# RejsaCAN_v2_5_-_Schematic.net
KiCad netlist of a schematic drawn in EasyEDA
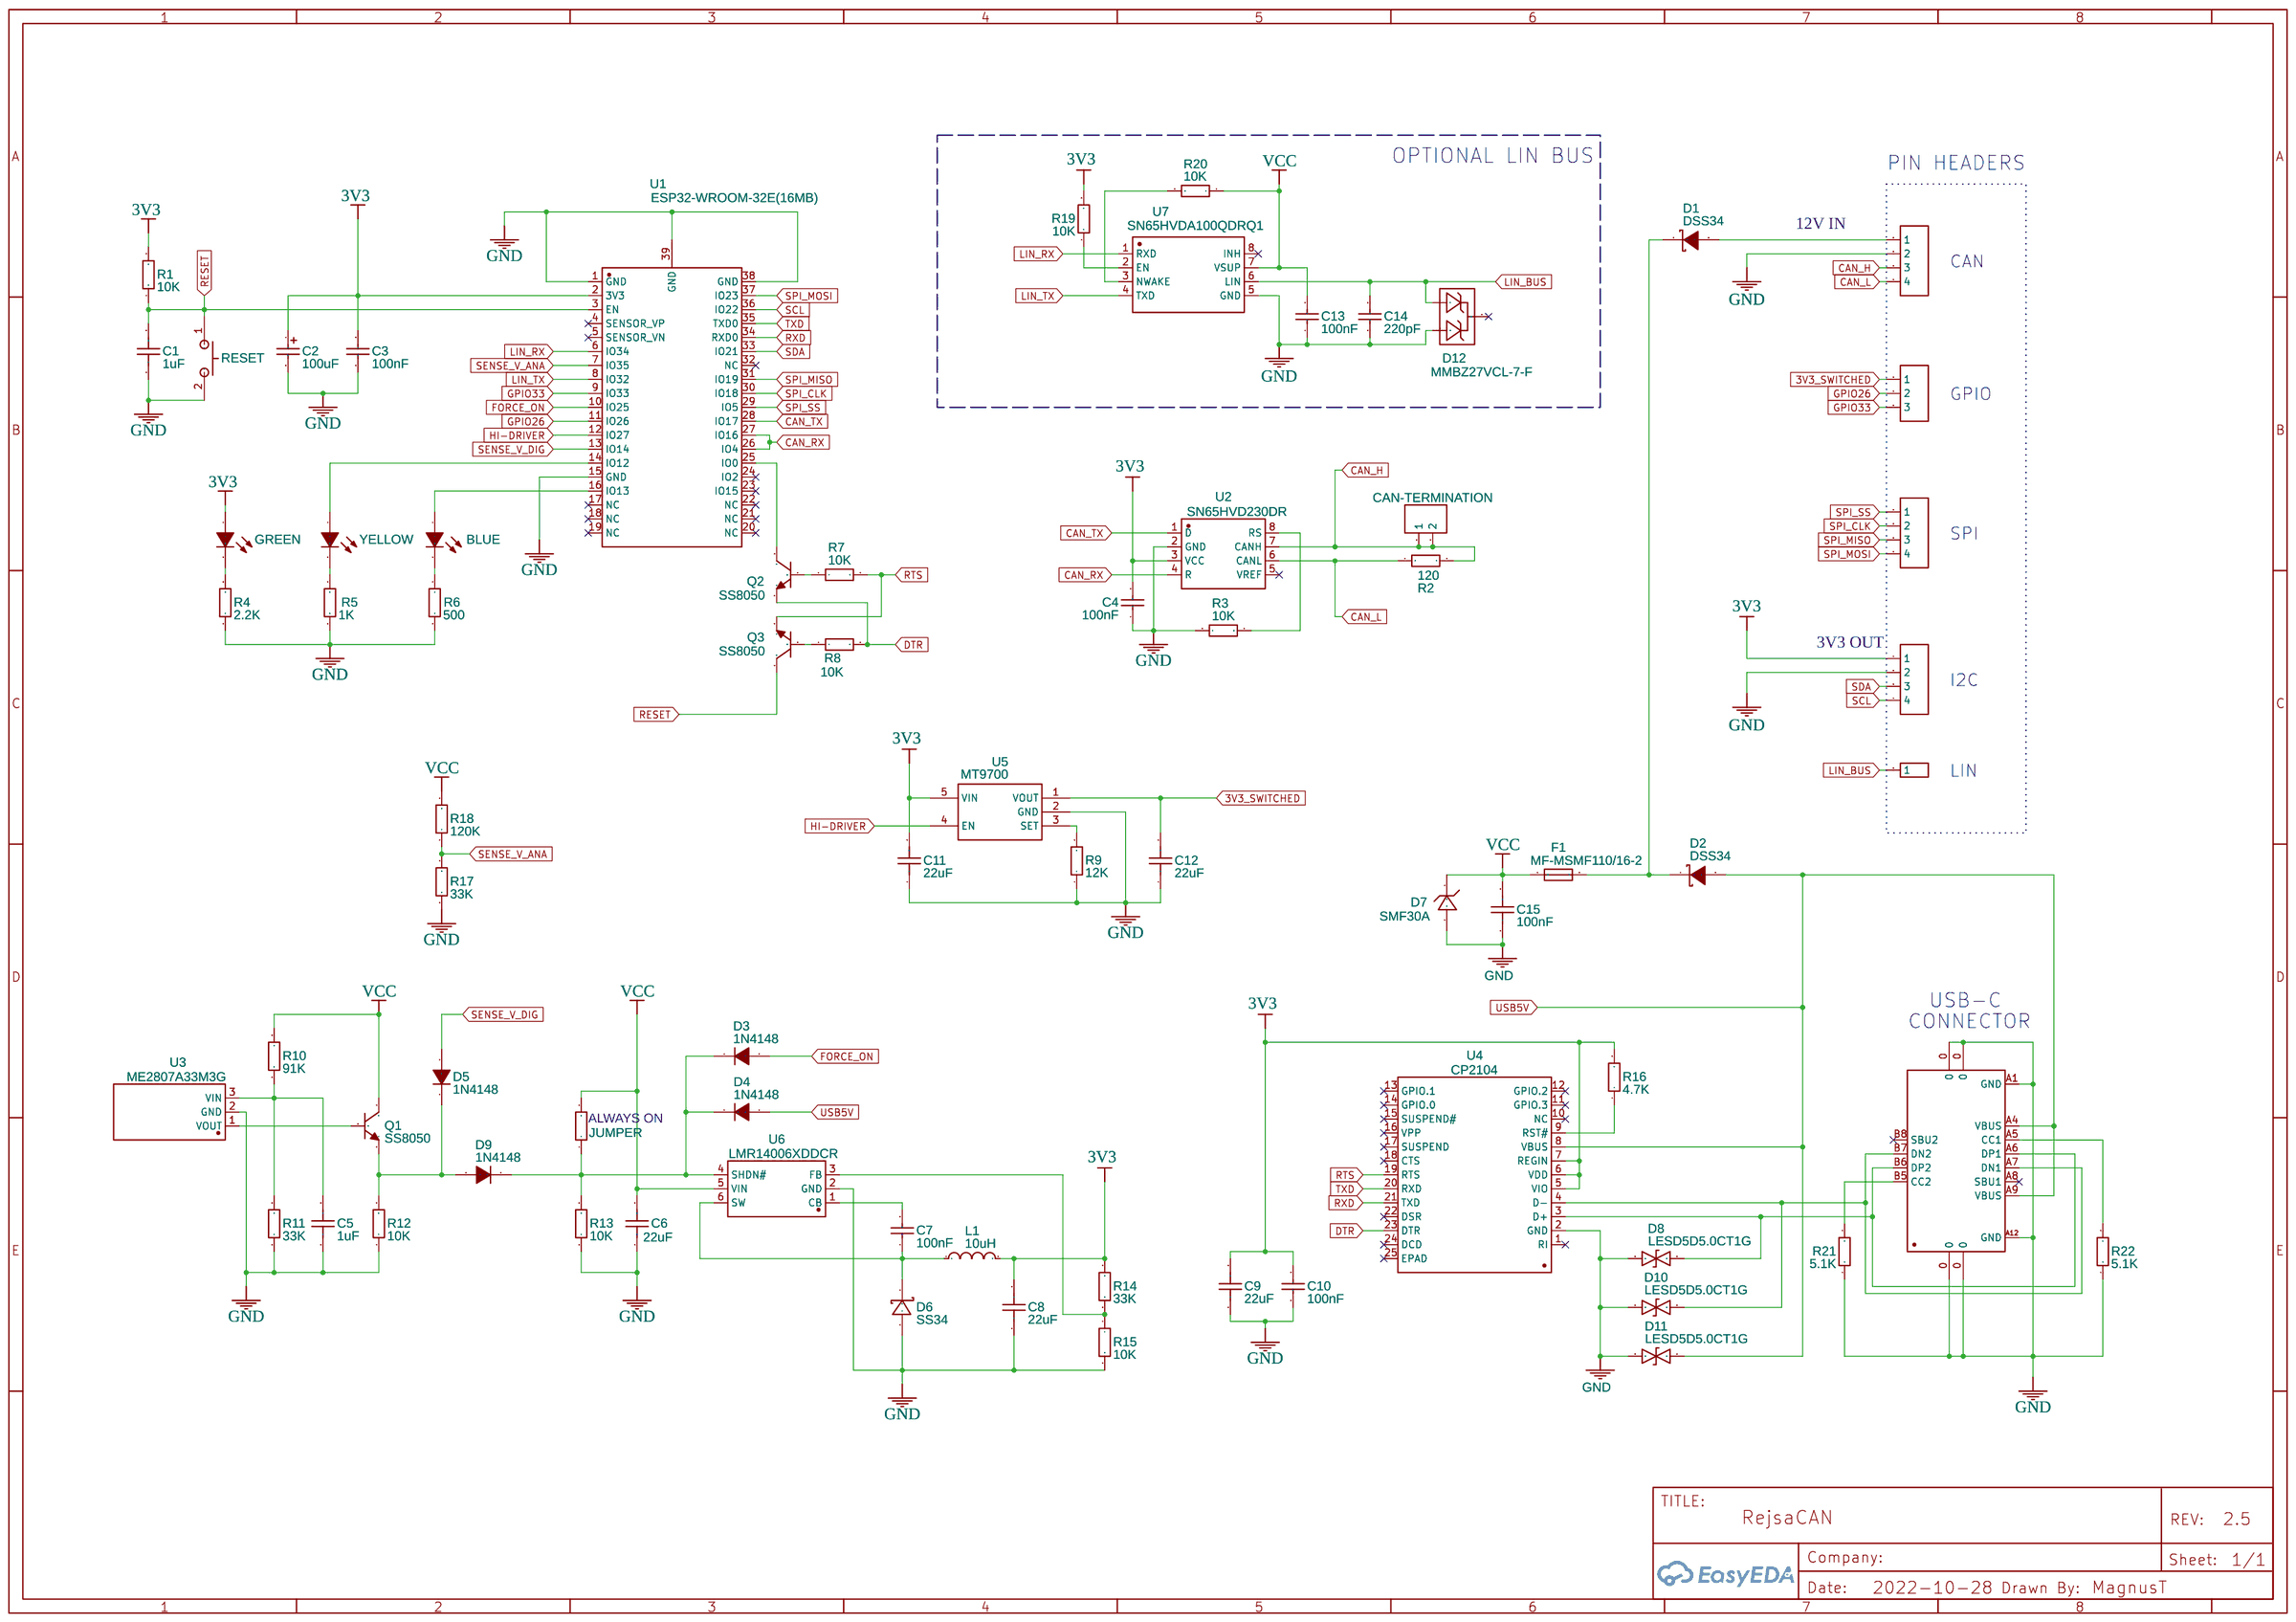
[diagram p0: schematic sheet]

(export (version "E")
  (design (tool "Eeschema 10.0.6"))
  (components
    (comp (ref "BLUE")
      (value "19-217/BHC-ZL1M2RY/3T")
      (fields (field (name "Manufacturer") "EVERLIGHT"))
      (libsource (lib "") (part "19-217/BHC-ZL1M2RY/3T"))
    )
    (comp (ref "C1")
      (value "1uF")
      (fields (field (name "Manufacturer Part") "CL05A105KA5NQNC") (field (name "Manufacturer") "SAMSUNG"))
      (libsource (lib "") (part "CL05A105KA5NQNC"))
    )
    (comp (ref "C2")
      (value "100uF")
      (fields (field (name "Manufacturer Part") "TAJB107K006RNJ") (field (name "Manufacturer") "AVX"))
      (libsource (lib "") (part "TAJB107K006RNJ"))
    )
    (comp (ref "C3")
      (value "100nF")
      (fields (field (name "Manufacturer Part") "CL05B104KO5NNNC") (field (name "Manufacturer") "SAMSUNG"))
      (libsource (lib "") (part "CL05B104KO5NNNC_1"))
    )
    (comp (ref "C4")
      (value "100nF")
      (fields (field (name "Manufacturer Part") "CL05B104KO5NNNC") (field (name "Manufacturer") "SAMSUNG"))
      (libsource (lib "") (part "CL05B104KO5NNNC"))
    )
    (comp (ref "C5")
      (value "1uF")
      (fields (field (name "Manufacturer Part") "CL05A105KA5NQNC") (field (name "Manufacturer") "SAMSUNG"))
      (libsource (lib "") (part "CL05A105KA5NQNC"))
    )
    (comp (ref "C6")
      (value "22uF")
      (fields
        (field (name "Manufacturer Part") "CL21A226MAYNNNE")
        (field (name "Manufacturer") "Samsung Electro-Mechanics")
      )
      (libsource (lib "") (part "CL21A226MAYNNNE"))
    )
    (comp (ref "C7")
      (value "100nF")
      (fields (field (name "Manufacturer Part") "CL05B104KO5NNNC") (field (name "Manufacturer") "SAMSUNG"))
      (libsource (lib "") (part "CL05B104KO5NNNC_1"))
    )
    (comp (ref "C8")
      (value "22uF")
      (fields (field (name "Manufacturer Part") "CL10A226MQ8NRNC") (field (name "Manufacturer") "SAMSUNG"))
      (libsource (lib "") (part "CL10A226MQ8NRNC"))
    )
    (comp (ref "C9")
      (value "22uF")
      (fields (field (name "Manufacturer Part") "CL10A226MQ8NRNC") (field (name "Manufacturer") "SAMSUNG"))
      (libsource (lib "") (part "CL10A226MQ8NRNC"))
    )
    (comp (ref "C10")
      (value "100nF")
      (fields (field (name "Manufacturer Part") "CL05B104KO5NNNC") (field (name "Manufacturer") "SAMSUNG"))
      (libsource (lib "") (part "CL05B104KO5NNNC_1"))
    )
    (comp (ref "C11")
      (value "22uF")
      (fields (field (name "Manufacturer Part") "CL10A226MQ8NRNC") (field (name "Manufacturer") "SAMSUNG"))
      (libsource (lib "") (part "CL10A226MQ8NRNC"))
    )
    (comp (ref "C12")
      (value "22uF")
      (fields (field (name "Manufacturer Part") "CL10A226MQ8NRNC") (field (name "Manufacturer") "SAMSUNG"))
      (libsource (lib "") (part "CL10A226MQ8NRNC"))
    )
    (comp (ref "C13")
      (value "100nF")
      (fields (field (name "Manufacturer Part") "CL05B104KO5NNNC") (field (name "Manufacturer") "SAMSUNG"))
      (libsource (lib "") (part "CL05B104KO5NNNC_1"))
    )
    (comp (ref "C14")
      (value "220pF")
      (fields (field (name "Manufacturer Part") "0402B221K500NT") (field (name "Manufacturer") "FH"))
      (libsource (lib "") (part "0402B221K500NT"))
    )
    (comp (ref "C15")
      (value "100nF")
      (fields
        (field (name "Manufacturer Part") "CL05B104KB54PNC")
        (field (name "Manufacturer") "Samsung Electro-Mechanics")
      )
      (libsource (lib "") (part "CL05B104KB54PNC"))
    )
    (comp (ref "CAN-TERMINATION") (value "HDR-M-2.54_1x2") (libsource (lib "") (part "HDR-M-2.54_1x2")))
    (comp (ref "D1")
      (value "DSS34")
      (fields (field (name "Manufacturer") "STARSEA"))
      (libsource (lib "") (part "DSS34"))
    )
    (comp (ref "D2")
      (value "DSS34")
      (fields (field (name "Manufacturer") "STARSEA"))
      (libsource (lib "") (part "DSS34"))
    )
    (comp (ref "D3")
      (value "1N4148")
      (fields (field (name "Manufacturer Part") "1N4148WS T4") (field (name "Manufacturer") "CJ"))
      (libsource (lib "") (part "1N4148WS T4"))
    )
    (comp (ref "D4")
      (value "1N4148")
      (fields (field (name "Manufacturer Part") "1N4148WS T4") (field (name "Manufacturer") "CJ"))
      (libsource (lib "") (part "1N4148WS T4"))
    )
    (comp (ref "D5")
      (value "1N4148")
      (fields (field (name "Manufacturer Part") "1N4148WS T4") (field (name "Manufacturer") "CJ"))
      (libsource (lib "") (part "1N4148WS T4_2"))
    )
    (comp (ref "D6")
      (value "SS34")
      (fields (field (name "Manufacturer") "MDD"))
      (libsource (lib "") (part "SS34_C8678"))
    )
    (comp (ref "D7")
      (value "SMF30A")
      (fields (field (name "Manufacturer") "DOWO"))
      (libsource (lib "") (part "SMF30A_C366558"))
    )
    (comp (ref "D8")
      (value "LESD5D5.0CT1G")
      (fields (field (name "Manufacturer") "Leshan Radio"))
      (libsource (lib "") (part "LESD5D5.0CT1G"))
    )
    (comp (ref "D9")
      (value "1N4148")
      (fields (field (name "Manufacturer Part") "1N4148WS T4") (field (name "Manufacturer") "CJ"))
      (libsource (lib "") (part "1N4148WS T4_1"))
    )
    (comp (ref "D10")
      (value "LESD5D5.0CT1G")
      (fields (field (name "Manufacturer") "Leshan Radio"))
      (libsource (lib "") (part "LESD5D5.0CT1G"))
    )
    (comp (ref "D11")
      (value "LESD5D5.0CT1G")
      (fields (field (name "Manufacturer") "Leshan Radio"))
      (libsource (lib "") (part "LESD5D5.0CT1G"))
    )
    (comp (ref "D12")
      (value "MMBZ27VCL-7-F")
      (fields (field (name "Manufacturer") "Diodes Incorporated"))
      (libsource (lib "") (part "MMBZ27VCL-7-F"))
    )
    (comp (ref "F1")
      (value "MF-MSMF110/16-2")
      (fields (field (name "Manufacturer") "BOURNS"))
      (libsource (lib "") (part "MF-MSMF110/16-2"))
    )
    (comp (ref "GREEN")
      (value "19-217/GHC-YR1S2/3T")
      (fields (field (name "Manufacturer") "EVERLIGHT"))
      (libsource (lib "") (part "19-217/GHC-YR1S2/3T"))
    )
    (comp (ref "J1") (value "HDR-M-2.54_1x4") (libsource (lib "") (part "HDR-M-2.54_1x4")))
    (comp (ref "J2") (value "HDR-M-2.54_1x4") (libsource (lib "") (part "HDR-M-2.54_1x4")))
    (comp (ref "J3") (value "HDR-M-2.54_1x4") (libsource (lib "") (part "HDR-M-2.54_1x4")))
    (comp (ref "J4") (value "HDR-M-2.54_1x3") (libsource (lib "") (part "HDR-M-2.54_1x3")))
    (comp (ref "J5") (value "HDR-M-2.54_1x1") (libsource (lib "") (part "HDR-M-2.54_1x1")))
    (comp (ref "JUMPER") (value "-") (libsource (lib "") (part "0402WGF3092TCE")))
    (comp (ref "L1")
      (value "10uH")
      (fields
        (field (name "Manufacturer Part") "SLP6028S100MTT")
        (field (name "Manufacturer") "Sunltech Tech")
      )
      (libsource (lib "") (part "SLP6028S100MTT"))
    )
    (comp (ref "Q1")
      (value "SS8050")
      (fields (field (name "Manufacturer") "CJ"))
      (libsource (lib "") (part "SS8050_C2150_2"))
    )
    (comp (ref "Q2")
      (value "SS8050")
      (fields (field (name "Manufacturer") "CJ"))
      (libsource (lib "") (part "SS8050_C2150_1"))
    )
    (comp (ref "Q3")
      (value "SS8050")
      (fields (field (name "Manufacturer") "CJ"))
      (libsource (lib "") (part "SS8050_C2150"))
    )
    (comp (ref "R1")
      (value "10K")
      (fields (field (name "Manufacturer Part") "0402WGF1002TCE") (field (name "Manufacturer") "UniOhm"))
      (libsource (lib "") (part "0402WGF1002TCE"))
    )
    (comp (ref "R2")
      (value "120")
      (fields (field (name "Manufacturer Part") "RTT061200FTP") (field (name "Manufacturer") "RALEC"))
      (libsource (lib "") (part "RTT061200FTP"))
    )
    (comp (ref "R3")
      (value "10K")
      (fields (field (name "Manufacturer Part") "0402WGF1002TCE") (field (name "Manufacturer") "UniOhm"))
      (libsource (lib "") (part "0402WGF1002TCE_1"))
    )
    (comp (ref "R4")
      (value "2.2K")
      (fields (field (name "Manufacturer Part") "0402WGF2201TCE") (field (name "Manufacturer") "UniOhm"))
      (libsource (lib "") (part "0402WGF2201TCE"))
    )
    (comp (ref "R5")
      (value "1K")
      (fields (field (name "Manufacturer Part") "0402WGF1001TCE") (field (name "Manufacturer") "UniOhm"))
      (libsource (lib "") (part "0402WGF1001TCE"))
    )
    (comp (ref "R6")
      (value "500")
      (fields (field (name "Manufacturer Part") "0402WGF4700TCE") (field (name "Manufacturer") "UniOhm"))
      (libsource (lib "") (part "0402WGF1001TCE"))
    )
    (comp (ref "R7")
      (value "10K")
      (fields (field (name "Manufacturer Part") "0402WGF1002TCE") (field (name "Manufacturer") "UniOhm"))
      (libsource (lib "") (part "0402WGF1002TCE_1"))
    )
    (comp (ref "R8")
      (value "10K")
      (fields (field (name "Manufacturer Part") "0402WGF1002TCE") (field (name "Manufacturer") "UniOhm"))
      (libsource (lib "") (part "0402WGF1002TCE_1"))
    )
    (comp (ref "R9")
      (value "12K")
      (fields (field (name "Manufacturer Part") "0402WGF1202TCE") (field (name "Manufacturer") "UniOhm"))
      (libsource (lib "") (part "0402WGF1202TCE"))
    )
    (comp (ref "R10")
      (value "91K")
      (fields (field (name "Manufacturer Part") "0402WGF9102TCE") (field (name "Manufacturer") "UniOhm"))
      (libsource (lib "") (part "0402WGF9102TCE"))
    )
    (comp (ref "R11")
      (value "33K")
      (fields (field (name "Manufacturer Part") "0402WGF3302TCE") (field (name "Manufacturer") "UniOhm"))
      (libsource (lib "") (part "0402WGF3302TCE"))
    )
    (comp (ref "R12")
      (value "10K")
      (fields (field (name "Manufacturer Part") "0402WGF1002TCE") (field (name "Manufacturer") "UniOhm"))
      (libsource (lib "") (part "0402WGF1002TCE"))
    )
    (comp (ref "R13")
      (value "10K")
      (fields (field (name "Manufacturer Part") "0402WGF1002TCE") (field (name "Manufacturer") "UniOhm"))
      (libsource (lib "") (part "0402WGF1002TCE"))
    )
    (comp (ref "R14")
      (value "33K")
      (fields (field (name "Manufacturer Part") "0402WGF3302TCE") (field (name "Manufacturer") "UniOhm"))
      (libsource (lib "") (part "0402WGF3302TCE"))
    )
    (comp (ref "R15")
      (value "10K")
      (fields (field (name "Manufacturer Part") "0402WGF1002TCE") (field (name "Manufacturer") "UniOhm"))
      (libsource (lib "") (part "0402WGF1002TCE_2"))
    )
    (comp (ref "R16")
      (value "4.7K")
      (fields (field (name "Manufacturer Part") "0402WGF4701TCE") (field (name "Manufacturer") "UniOhm"))
      (libsource (lib "") (part "0402WGF4701TCE"))
    )
    (comp (ref "R17")
      (value "33K")
      (fields (field (name "Manufacturer Part") "0402WGF3302TCE") (field (name "Manufacturer") "UniOhm"))
      (libsource (lib "") (part "0402WGF3302TCE"))
    )
    (comp (ref "R18")
      (value "120K")
      (fields (field (name "Manufacturer Part") "0402WGF1203TCE") (field (name "Manufacturer") "UniOhm"))
      (libsource (lib "") (part "0402WGF1203TCE"))
    )
    (comp (ref "R19")
      (value "10K")
      (fields (field (name "Manufacturer Part") "0402WGF1002TCE") (field (name "Manufacturer") "UniOhm"))
      (libsource (lib "") (part "0402WGF1002TCE"))
    )
    (comp (ref "R20")
      (value "10K")
      (fields (field (name "Manufacturer Part") "0402WGF1002TCE") (field (name "Manufacturer") "UniOhm"))
      (libsource (lib "") (part "0402WGF1002TCE_3"))
    )
    (comp (ref "R21")
      (value "5.1K")
      (fields (field (name "Manufacturer Part") "0402WGF5101TCE") (field (name "Manufacturer") "UniOhm"))
      (libsource (lib "") (part "0402WGF5101TCE"))
    )
    (comp (ref "R22")
      (value "5.1K")
      (fields (field (name "Manufacturer Part") "0402WGF5101TCE") (field (name "Manufacturer") "UniOhm"))
      (libsource (lib "") (part "0402WGF5101TCE"))
    )
    (comp (ref "RESET")
      (value "GT-TC029B-H025-L1N")
      (fields (field (name "Manufacturer") "G-Switch"))
      (libsource (lib "") (part "GT-TC029B-H025-L1N"))
    )
    (comp (ref "U1")
      (value "ESP32-WROOM-32E(16MB)")
      (fields (field (name "Manufacturer") "Espressif Systems"))
      (libsource (lib "") (part "ESP32-WROOM-32E(16MB)"))
    )
    (comp (ref "U2")
      (value "SN65HVD230DR")
      (fields (field (name "Manufacturer") "TI"))
      (libsource (lib "") (part "SN65HVD230DR"))
    )
    (comp (ref "U3")
      (value "ME2807A33M3G")
      (fields (field (name "Manufacturer") "Nanjing Micro One Elec"))
      (libsource (lib "") (part "ME2807A33M3G"))
    )
    (comp (ref "U4")
      (value "CP2104")
      (fields (field (name "Manufacturer Part") "CP2104-F03-GM") (field (name "Manufacturer") "SILICON LABS"))
      (libsource (lib "") (part "CP2104-F03-GM"))
    )
    (comp (ref "U5")
      (value "MT9700")
      (fields (field (name "Manufacturer") "AEROSEMI"))
      (libsource (lib "") (part "MT9700"))
    )
    (comp (ref "U6")
      (value "LMR14006XDDCR")
      (fields (field (name "Manufacturer") "Texas Instruments"))
      (libsource (lib "") (part "LMR14006XDDCR"))
    )
    (comp (ref "U7")
      (value "SN65HVDA100QDRQ1")
      (fields (field (name "Manufacturer") "TI"))
      (libsource (lib "") (part "SN65HVDA100QDRQ1"))
    )
    (comp (ref "USB-C")
      (value "USB3.1C16PFSMT")
      (fields (field (name "Manufacturer") "LCSC"))
      (libsource (lib "") (part "USB3.1C16PFSMT"))
    )
    (comp (ref "YELLOW")
      (value "19-213/Y2C-CQ2R2L/3T(CY)")
      (fields (field (name "Manufacturer") "EVERLIGHT"))
      (libsource (lib "") (part "19-213/Y2C-CQ2R2L/3T(CY)"))
    )
  )
  (nets
    (net (code "1") (name "3V3") (class "Default")
      (node (ref "C10") (pin "2") (pinfunction "2_2") (pintype "input"))
      (node (ref "C11") (pin "2") (pinfunction "2_2") (pintype "unspecified"))
      (node (ref "C2") (pin "1") (pinfunction "1_1") (pintype "input"))
      (node (ref "C3") (pin "2") (pinfunction "2_2") (pintype "input"))
      (node (ref "C4") (pin "2") (pinfunction "2_2") (pintype "input"))
      (node (ref "C8") (pin "2") (pinfunction "2_2") (pintype "unspecified"))
      (node (ref "C9") (pin "2") (pinfunction "2_2") (pintype "unspecified"))
      (node (ref "GREEN") (pin "1") (pinfunction "A_1") (pintype "input"))
      (node (ref "J2") (pin "1") (pinfunction "1_1") (pintype "unspecified"))
      (node (ref "L1") (pin "2") (pinfunction "2_2") (pintype "unspecified"))
      (node (ref "R1") (pin "2") (pinfunction "2_2") (pintype "input"))
      (node (ref "R14") (pin "2") (pinfunction "2_2") (pintype "input"))
      (node (ref "R16") (pin "2") (pinfunction "2_2") (pintype "input"))
      (node (ref "R19") (pin "2") (pinfunction "2_2") (pintype "input"))
      (node (ref "U1") (pin "2") (pinfunction "3V3_2") (pintype "unspecified"))
      (node (ref "U2") (pin "3") (pinfunction "VCC_3") (pintype "unspecified"))
      (node (ref "U4") (pin "5") (pinfunction "VIO_5") (pintype "unspecified"))
      (node (ref "U4") (pin "6") (pinfunction "VDD_6") (pintype "unspecified"))
      (node (ref "U4") (pin "7") (pinfunction "REGIN_7") (pintype "unspecified"))
      (node (ref "U5") (pin "5") (pinfunction "VIN_5") (pintype "unspecified"))
    )
    (net (code "2") (name "3V3_SWITCHED") (class "Default")
      (node (ref "C12") (pin "2") (pinfunction "2_2") (pintype "unspecified"))
      (node (ref "J4") (pin "1") (pinfunction "1_1") (pintype "input"))
      (node (ref "U5") (pin "1") (pinfunction "VOUT_1") (pintype "unspecified"))
    )
    (net (code "3") (name "CAN_H") (class "Default")
      (node (ref "CAN-TERMINATION") (pin "1") (pinfunction "1_1") (pintype "unspecified"))
      (node (ref "CAN-TERMINATION") (pin "2") (pinfunction "2_2") (pintype "unspecified"))
      (node (ref "J1") (pin "3") (pinfunction "3_3") (pintype "unspecified"))
      (node (ref "R2") (pin "2") (pinfunction "2_2") (pintype "unspecified"))
      (node (ref "U2") (pin "7") (pinfunction "CANH_7") (pintype "unspecified"))
    )
    (net (code "4") (name "CAN_L") (class "Default")
      (node (ref "J1") (pin "4") (pinfunction "4_4") (pintype "unspecified"))
      (node (ref "R2") (pin "1") (pinfunction "1_1") (pintype "unspecified"))
      (node (ref "U2") (pin "6") (pinfunction "CANL_6") (pintype "unspecified"))
    )
    (net (code "5") (name "CAN_RX") (class "Default")
      (node (ref "U1") (pin "26") (pinfunction "IO4_26") (pintype "unspecified"))
      (node (ref "U1") (pin "27") (pinfunction "IO16_27") (pintype "unspecified"))
      (node (ref "U2") (pin "4") (pinfunction "R_4") (pintype "unspecified"))
    )
    (net (code "6") (name "CAN_TX") (class "Default")
      (node (ref "U1") (pin "28") (pinfunction "IO17_28") (pintype "unspecified"))
      (node (ref "U2") (pin "1") (pinfunction "D_1") (pintype "unspecified"))
    )
    (net (code "7") (name "DTR") (class "Default")
      (node (ref "Q2") (pin "2") (pinfunction "E_2") (pintype "unspecified"))
      (node (ref "R8") (pin "2") (pinfunction "2_2") (pintype "input"))
      (node (ref "U4") (pin "23") (pinfunction "DTR_23") (pintype "unspecified"))
    )
    (net (code "8") (name "FORCE_ON") (class "Default")
      (node (ref "D3") (pin "2") (pinfunction "A_2") (pintype "unspecified"))
      (node (ref "U1") (pin "10") (pinfunction "IO25_10") (pintype "unspecified"))
    )
    (net (code "9") (name "GND") (class "Default")
      (node (ref "C1") (pin "1") (pinfunction "1_1") (pintype "unspecified"))
      (node (ref "C10") (pin "1") (pinfunction "1_1") (pintype "input"))
      (node (ref "C11") (pin "1") (pinfunction "1_1") (pintype "unspecified"))
      (node (ref "C12") (pin "1") (pinfunction "1_1") (pintype "unspecified"))
      (node (ref "C13") (pin "1") (pinfunction "1_1") (pintype "input"))
      (node (ref "C14") (pin "1") (pinfunction "1_1") (pintype "input"))
      (node (ref "C15") (pin "1") (pinfunction "1_1") (pintype "unspecified"))
      (node (ref "C2") (pin "2") (pinfunction "2_2") (pintype "input"))
      (node (ref "C3") (pin "1") (pinfunction "1_1") (pintype "input"))
      (node (ref "C4") (pin "1") (pinfunction "1_1") (pintype "input"))
      (node (ref "C5") (pin "1") (pinfunction "1_1") (pintype "unspecified"))
      (node (ref "C6") (pin "1") (pinfunction "1_1") (pintype "unspecified"))
      (node (ref "C8") (pin "1") (pinfunction "1_1") (pintype "unspecified"))
      (node (ref "C9") (pin "1") (pinfunction "1_1") (pintype "unspecified"))
      (node (ref "D10") (pin "2") (pinfunction "2_2") (pintype "unspecified"))
      (node (ref "D11") (pin "2") (pinfunction "2_2") (pintype "unspecified"))
      (node (ref "D12") (pin "2") (pinfunction "2_2") (pintype "unspecified"))
      (node (ref "D6") (pin "2") (pinfunction "A_2") (pintype "unspecified"))
      (node (ref "D7") (pin "2") (pinfunction "2_2") (pintype "unspecified"))
      (node (ref "D8") (pin "2") (pinfunction "2_2") (pintype "unspecified"))
      (node (ref "J1") (pin "2") (pinfunction "2_2") (pintype "unspecified"))
      (node (ref "J2") (pin "2") (pinfunction "2_2") (pintype "unspecified"))
      (node (ref "R11") (pin "1") (pinfunction "1_1") (pintype "input"))
      (node (ref "R12") (pin "1") (pinfunction "1_1") (pintype "input"))
      (node (ref "R13") (pin "1") (pinfunction "1_1") (pintype "input"))
      (node (ref "R15") (pin "2") (pinfunction "2_2") (pintype "input"))
      (node (ref "R17") (pin "1") (pinfunction "1_1") (pintype "input"))
      (node (ref "R21") (pin "1") (pinfunction "1_1") (pintype "input"))
      (node (ref "R22") (pin "1") (pinfunction "1_1") (pintype "input"))
      (node (ref "R3") (pin "1") (pinfunction "1_1") (pintype "input"))
      (node (ref "R4") (pin "1") (pinfunction "1_1") (pintype "input"))
      (node (ref "R5") (pin "2") (pinfunction "2_2") (pintype "input"))
      (node (ref "R6") (pin "2") (pinfunction "2_2") (pintype "input"))
      (node (ref "R9") (pin "1") (pinfunction "1_1") (pintype "input"))
      (node (ref "RESET") (pin "2") (pinfunction "2_2") (pintype "unspecified"))
      (node (ref "U1") (pin "1") (pinfunction "GND_1") (pintype "unspecified"))
      (node (ref "U1") (pin "15") (pinfunction "GND_15") (pintype "unspecified"))
      (node (ref "U1") (pin "38") (pinfunction "GND_38") (pintype "unspecified"))
      (node (ref "U1") (pin "39") (pinfunction "GND_39") (pintype "unspecified"))
      (node (ref "U2") (pin "2") (pinfunction "GND_2") (pintype "unspecified"))
      (node (ref "U3") (pin "2") (pinfunction "GND_2") (pintype "unspecified"))
      (node (ref "U4") (pin "2") (pinfunction "GND_2") (pintype "unspecified"))
      (node (ref "U5") (pin "2") (pinfunction "GND_2") (pintype "unspecified"))
      (node (ref "U6") (pin "2") (pinfunction "GND_2") (pintype "unspecified"))
      (node (ref "U7") (pin "5") (pinfunction "GND_5") (pintype "unspecified"))
      (node (ref "USB-C") (pin "0") (pinfunction "0_0") (pintype "unspecified"))
      (node (ref "USB-C") (pin "A1") (pinfunction "GND_A1") (pintype "unspecified"))
      (node (ref "USB-C") (pin "A12") (pinfunction "GND_A12") (pintype "unspecified"))
    )
    (net (code "10") (name "GPIO26") (class "Default")
      (node (ref "J4") (pin "2") (pinfunction "2_2") (pintype "input"))
      (node (ref "U1") (pin "11") (pinfunction "IO26_11") (pintype "unspecified"))
    )
    (net (code "11") (name "GPIO33") (class "Default")
      (node (ref "J4") (pin "3") (pinfunction "3_3") (pintype "input"))
      (node (ref "U1") (pin "9") (pinfunction "IO33_9") (pintype "unspecified"))
    )
    (net (code "12") (name "HI-DRIVER") (class "Default")
      (node (ref "U1") (pin "12") (pinfunction "IO27_12") (pintype "unspecified"))
      (node (ref "U5") (pin "4") (pinfunction "EN_4") (pintype "unspecified"))
    )
    (net (code "13") (name "LIN_BUS") (class "Default")
      (node (ref "C14") (pin "2") (pinfunction "2_2") (pintype "input"))
      (node (ref "D12") (pin "1") (pinfunction "1_1") (pintype "unspecified"))
      (node (ref "J5") (pin "1") (pinfunction "1_1") (pintype "input"))
      (node (ref "U7") (pin "6") (pinfunction "LIN_6") (pintype "unspecified"))
    )
    (net (code "14") (name "LIN_RX") (class "Default")
      (node (ref "U1") (pin "6") (pinfunction "IO34_6") (pintype "unspecified"))
      (node (ref "U7") (pin "1") (pinfunction "RXD_1") (pintype "unspecified"))
    )
    (net (code "15") (name "LIN_TX") (class "Default")
      (node (ref "U1") (pin "8") (pinfunction "IO32_8") (pintype "unspecified"))
      (node (ref "U7") (pin "4") (pinfunction "TXD_4") (pintype "unspecified"))
    )
    (net (code "16") (name "Net-(BLUE-A)") (class "Default")
      (node (ref "BLUE") (pin "1") (pinfunction "A_1") (pintype "input"))
      (node (ref "U1") (pin "16") (pinfunction "IO13_16") (pintype "unspecified"))
    )
    (net (code "17") (name "Net-(BLUE-C)") (class "Default")
      (node (ref "BLUE") (pin "2") (pinfunction "C_2") (pintype "input"))
      (node (ref "R6") (pin "1") (pinfunction "1_1") (pintype "input"))
    )
    (net (code "18") (name "Net-(D1-A)") (class "Default")
      (node (ref "D1") (pin "2") (pinfunction "A_2") (pintype "unspecified"))
      (node (ref "J1") (pin "1") (pinfunction "1_1") (pintype "unspecified"))
    )
    (net (code "19") (name "Net-(D1-K)") (class "Default")
      (node (ref "D1") (pin "1") (pinfunction "K_1") (pintype "unspecified"))
      (node (ref "D2") (pin "1") (pinfunction "K_1") (pintype "unspecified"))
      (node (ref "F1") (pin "2") (pinfunction "2_2") (pintype "unspecified"))
    )
    (net (code "20") (name "Net-(D3-K)") (class "Default")
      (node (ref "D3") (pin "1") (pinfunction "K_1") (pintype "unspecified"))
      (node (ref "D4") (pin "1") (pinfunction "K_1") (pintype "unspecified"))
      (node (ref "D9") (pin "1") (pinfunction "K_1") (pintype "unspecified"))
      (node (ref "JUMPER") (pin "1") (pinfunction "1_1") (pintype "unspecified"))
      (node (ref "R13") (pin "2") (pinfunction "2_2") (pintype "input"))
      (node (ref "U6") (pin "4") (pinfunction "SHDN#_4") (pintype "unspecified"))
    )
    (net (code "21") (name "Net-(D5-K)") (class "Default")
      (node (ref "D5") (pin "1") (pinfunction "K_1") (pintype "unspecified"))
      (node (ref "D9") (pin "2") (pinfunction "A_2") (pintype "unspecified"))
      (node (ref "Q1") (pin "2") (pinfunction "E_2") (pintype "unspecified"))
      (node (ref "R12") (pin "2") (pinfunction "2_2") (pintype "input"))
    )
    (net (code "22") (name "Net-(D6-K)") (class "Default")
      (node (ref "C7") (pin "1") (pinfunction "1_1") (pintype "input"))
      (node (ref "D6") (pin "1") (pinfunction "K_1") (pintype "unspecified"))
      (node (ref "L1") (pin "1") (pinfunction "1_1") (pintype "unspecified"))
      (node (ref "U6") (pin "6") (pinfunction "SW_6") (pintype "unspecified"))
    )
    (net (code "23") (name "Net-(GREEN-C)") (class "Default")
      (node (ref "GREEN") (pin "2") (pinfunction "C_2") (pintype "input"))
      (node (ref "R4") (pin "2") (pinfunction "2_2") (pintype "input"))
    )
    (net (code "24") (name "Net-(Q1-B)") (class "Default")
      (node (ref "Q1") (pin "1") (pinfunction "B_1") (pintype "unspecified"))
      (node (ref "U3") (pin "1") (pinfunction "VOUT_1") (pintype "unspecified"))
    )
    (net (code "25") (name "Net-(Q2-B)") (class "Default")
      (node (ref "Q2") (pin "1") (pinfunction "B_1") (pintype "unspecified"))
      (node (ref "R7") (pin "1") (pinfunction "1_1") (pintype "input"))
    )
    (net (code "26") (name "Net-(Q2-C)") (class "Default")
      (node (ref "Q2") (pin "3") (pinfunction "C_3") (pintype "unspecified"))
      (node (ref "U1") (pin "25") (pinfunction "IO0_25") (pintype "unspecified"))
    )
    (net (code "27") (name "Net-(Q3-B)") (class "Default")
      (node (ref "Q3") (pin "1") (pinfunction "B_1") (pintype "unspecified"))
      (node (ref "R8") (pin "1") (pinfunction "1_1") (pintype "input"))
    )
    (net (code "28") (name "Net-(U1-IO12)") (class "Default")
      (node (ref "U1") (pin "14") (pinfunction "IO12_14") (pintype "unspecified"))
      (node (ref "YELLOW") (pin "1") (pinfunction "A_1") (pintype "input"))
    )
    (net (code "29") (name "Net-(U2-RS)") (class "Default")
      (node (ref "R3") (pin "2") (pinfunction "2_2") (pintype "input"))
      (node (ref "U2") (pin "8") (pinfunction "RS_8") (pintype "unspecified"))
    )
    (net (code "30") (name "Net-(U3-VIN)") (class "Default")
      (node (ref "C5") (pin "2") (pinfunction "2_2") (pintype "unspecified"))
      (node (ref "R10") (pin "1") (pinfunction "1_1") (pintype "input"))
      (node (ref "R11") (pin "2") (pinfunction "2_2") (pintype "input"))
      (node (ref "U3") (pin "3") (pinfunction "VIN_3") (pintype "unspecified"))
    )
    (net (code "31") (name "Net-(U4-D+)") (class "Default")
      (node (ref "D8") (pin "1") (pinfunction "1_1") (pintype "unspecified"))
      (node (ref "U4") (pin "3") (pinfunction "D+_3") (pintype "unspecified"))
      (node (ref "USB-C") (pin "A6") (pinfunction "DP1_A6") (pintype "unspecified"))
      (node (ref "USB-C") (pin "B6") (pinfunction "DP2_B6") (pintype "unspecified"))
    )
    (net (code "32") (name "Net-(U4-D-)") (class "Default")
      (node (ref "D10") (pin "1") (pinfunction "1_1") (pintype "unspecified"))
      (node (ref "U4") (pin "4") (pinfunction "D-_4") (pintype "unspecified"))
      (node (ref "USB-C") (pin "A7") (pinfunction "DN1_A7") (pintype "unspecified"))
      (node (ref "USB-C") (pin "B7") (pinfunction "DN2_B7") (pintype "unspecified"))
    )
    (net (code "33") (name "Net-(U4-RST#)") (class "Default")
      (node (ref "R16") (pin "1") (pinfunction "1_1") (pintype "input"))
      (node (ref "U4") (pin "9") (pinfunction "RST#_9") (pintype "unspecified"))
    )
    (net (code "34") (name "Net-(U5-SET)") (class "Default")
      (node (ref "R9") (pin "2") (pinfunction "2_2") (pintype "input"))
      (node (ref "U5") (pin "3") (pinfunction "SET_3") (pintype "unspecified"))
    )
    (net (code "35") (name "Net-(U6-CB)") (class "Default")
      (node (ref "C7") (pin "2") (pinfunction "2_2") (pintype "input"))
      (node (ref "U6") (pin "1") (pinfunction "CB_1") (pintype "unspecified"))
    )
    (net (code "36") (name "Net-(U6-FB)") (class "Default")
      (node (ref "R14") (pin "1") (pinfunction "1_1") (pintype "input"))
      (node (ref "R15") (pin "1") (pinfunction "1_1") (pintype "input"))
      (node (ref "U6") (pin "3") (pinfunction "FB_3") (pintype "unspecified"))
    )
    (net (code "37") (name "Net-(U7-EN)") (class "Default")
      (node (ref "R19") (pin "1") (pinfunction "1_1") (pintype "input"))
      (node (ref "U7") (pin "2") (pinfunction "EN_2") (pintype "unspecified"))
    )
    (net (code "38") (name "Net-(U7-NWAKE)") (class "Default")
      (node (ref "R20") (pin "2") (pinfunction "2_2") (pintype "input"))
      (node (ref "U7") (pin "3") (pinfunction "NWAKE_3") (pintype "unspecified"))
    )
    (net (code "39") (name "Net-(USB-C-CC1)") (class "Default")
      (node (ref "R22") (pin "2") (pinfunction "2_2") (pintype "input"))
      (node (ref "USB-C") (pin "A5") (pinfunction "CC1_A5") (pintype "unspecified"))
    )
    (net (code "40") (name "Net-(USB-C-CC2)") (class "Default")
      (node (ref "R21") (pin "2") (pinfunction "2_2") (pintype "input"))
      (node (ref "USB-C") (pin "B5") (pinfunction "CC2_B5") (pintype "unspecified"))
    )
    (net (code "41") (name "Net-(YELLOW-C)") (class "Default")
      (node (ref "R5") (pin "1") (pinfunction "1_1") (pintype "input"))
      (node (ref "YELLOW") (pin "2") (pinfunction "C_2") (pintype "input"))
    )
    (net (code "42") (name "RESET") (class "Default")
      (node (ref "C1") (pin "2") (pinfunction "2_2") (pintype "unspecified"))
      (node (ref "Q3") (pin "3") (pinfunction "C_3") (pintype "unspecified"))
      (node (ref "R1") (pin "1") (pinfunction "1_1") (pintype "input"))
      (node (ref "RESET") (pin "1") (pinfunction "1_1") (pintype "unspecified"))
      (node (ref "U1") (pin "3") (pinfunction "EN_3") (pintype "unspecified"))
    )
    (net (code "43") (name "RTS") (class "Default")
      (node (ref "Q3") (pin "2") (pinfunction "E_2") (pintype "unspecified"))
      (node (ref "R7") (pin "2") (pinfunction "2_2") (pintype "input"))
      (node (ref "U4") (pin "19") (pinfunction "RTS_19") (pintype "unspecified"))
    )
    (net (code "44") (name "RXD") (class "Default")
      (node (ref "U1") (pin "34") (pinfunction "RXD0_34") (pintype "unspecified"))
      (node (ref "U4") (pin "21") (pinfunction "TXD_21") (pintype "unspecified"))
    )
    (net (code "45") (name "SCL") (class "Default")
      (node (ref "J2") (pin "4") (pinfunction "4_4") (pintype "unspecified"))
      (node (ref "U1") (pin "36") (pinfunction "IO22_36") (pintype "unspecified"))
    )
    (net (code "46") (name "SDA") (class "Default")
      (node (ref "J2") (pin "3") (pinfunction "3_3") (pintype "unspecified"))
      (node (ref "U1") (pin "33") (pinfunction "IO21_33") (pintype "unspecified"))
    )
    (net (code "47") (name "SENSE_V_ANA") (class "Default")
      (node (ref "R17") (pin "2") (pinfunction "2_2") (pintype "input"))
      (node (ref "R18") (pin "1") (pinfunction "1_1") (pintype "input"))
      (node (ref "U1") (pin "7") (pinfunction "IO35_7") (pintype "unspecified"))
    )
    (net (code "48") (name "SENSE_V_DIG") (class "Default")
      (node (ref "D5") (pin "2") (pinfunction "A_2") (pintype "unspecified"))
      (node (ref "U1") (pin "13") (pinfunction "IO14_13") (pintype "unspecified"))
    )
    (net (code "49") (name "SPI_CLK") (class "Default")
      (node (ref "J3") (pin "2") (pinfunction "2_2") (pintype "unspecified"))
      (node (ref "U1") (pin "30") (pinfunction "IO18_30") (pintype "unspecified"))
    )
    (net (code "50") (name "SPI_MISO") (class "Default")
      (node (ref "J3") (pin "3") (pinfunction "3_3") (pintype "unspecified"))
      (node (ref "U1") (pin "31") (pinfunction "IO19_31") (pintype "unspecified"))
    )
    (net (code "51") (name "SPI_MOSI") (class "Default")
      (node (ref "J3") (pin "4") (pinfunction "4_4") (pintype "unspecified"))
      (node (ref "U1") (pin "37") (pinfunction "IO23_37") (pintype "unspecified"))
    )
    (net (code "52") (name "SPI_SS") (class "Default")
      (node (ref "J3") (pin "1") (pinfunction "1_1") (pintype "unspecified"))
      (node (ref "U1") (pin "29") (pinfunction "IO5_29") (pintype "unspecified"))
    )
    (net (code "53") (name "TXD") (class "Default")
      (node (ref "U1") (pin "35") (pinfunction "TXD0_35") (pintype "unspecified"))
      (node (ref "U4") (pin "20") (pinfunction "RXD_20") (pintype "unspecified"))
    )
    (net (code "54") (name "USB5V") (class "Default")
      (node (ref "D11") (pin "1") (pinfunction "1_1") (pintype "unspecified"))
      (node (ref "D2") (pin "2") (pinfunction "A_2") (pintype "unspecified"))
      (node (ref "D4") (pin "2") (pinfunction "A_2") (pintype "unspecified"))
      (node (ref "U4") (pin "8") (pinfunction "VBUS_8") (pintype "unspecified"))
      (node (ref "USB-C") (pin "A4") (pinfunction "VBUS_A4") (pintype "unspecified"))
      (node (ref "USB-C") (pin "A9") (pinfunction "VBUS_A9") (pintype "unspecified"))
    )
    (net (code "55") (name "VCC") (class "Default")
      (node (ref "C13") (pin "2") (pinfunction "2_2") (pintype "input"))
      (node (ref "C15") (pin "2") (pinfunction "2_2") (pintype "unspecified"))
      (node (ref "C6") (pin "2") (pinfunction "2_2") (pintype "unspecified"))
      (node (ref "D7") (pin "1") (pinfunction "1_1") (pintype "unspecified"))
      (node (ref "F1") (pin "1") (pinfunction "1_1") (pintype "unspecified"))
      (node (ref "JUMPER") (pin "2") (pinfunction "2_2") (pintype "unspecified"))
      (node (ref "Q1") (pin "3") (pinfunction "C_3") (pintype "unspecified"))
      (node (ref "R10") (pin "2") (pinfunction "2_2") (pintype "input"))
      (node (ref "R18") (pin "2") (pinfunction "2_2") (pintype "input"))
      (node (ref "R20") (pin "1") (pinfunction "1_1") (pintype "input"))
      (node (ref "U6") (pin "5") (pinfunction "VIN_5") (pintype "unspecified"))
      (node (ref "U7") (pin "7") (pinfunction "VSUP_7") (pintype "unspecified"))
    )
    (net (code "56") (name "unconnected-(D12-Pad3)") (class "Default")
      (node (ref "D12") (pin "3") (pinfunction "3_3") (pintype "unspecified+no_connect"))
    )
    (net (code "57") (name "unconnected-(U1-IO2-Pad24)") (class "Default")
      (node (ref "U1") (pin "24") (pinfunction "IO2_24") (pintype "unspecified+no_connect"))
    )
    (net (code "58") (name "unconnected-(U1-IO15-Pad23)") (class "Default")
      (node (ref "U1") (pin "23") (pinfunction "IO15_23") (pintype "unspecified+no_connect"))
    )
    (net (code "59") (name "unconnected-(U1-NC-Pad17)") (class "Default")
      (node (ref "U1") (pin "17") (pinfunction "NC_17") (pintype "unspecified+no_connect"))
    )
    (net (code "60") (name "unconnected-(U1-NC-Pad18)") (class "Default")
      (node (ref "U1") (pin "18") (pinfunction "NC_18") (pintype "unspecified+no_connect"))
    )
    (net (code "61") (name "unconnected-(U1-NC-Pad19)") (class "Default")
      (node (ref "U1") (pin "19") (pinfunction "NC_19") (pintype "unspecified+no_connect"))
    )
    (net (code "62") (name "unconnected-(U1-NC-Pad20)") (class "Default")
      (node (ref "U1") (pin "20") (pinfunction "NC_20") (pintype "unspecified+no_connect"))
    )
    (net (code "63") (name "unconnected-(U1-NC-Pad21)") (class "Default")
      (node (ref "U1") (pin "21") (pinfunction "NC_21") (pintype "unspecified+no_connect"))
    )
    (net (code "64") (name "unconnected-(U1-NC-Pad22)") (class "Default")
      (node (ref "U1") (pin "22") (pinfunction "NC_22") (pintype "unspecified+no_connect"))
    )
    (net (code "65") (name "unconnected-(U1-NC-Pad32)") (class "Default")
      (node (ref "U1") (pin "32") (pinfunction "NC_32") (pintype "unspecified+no_connect"))
    )
    (net (code "66") (name "unconnected-(U1-SENSOR_VN-Pad5)") (class "Default")
      (node (ref "U1") (pin "5") (pinfunction "SENSOR_VN_5") (pintype "unspecified+no_connect"))
    )
    (net (code "67") (name "unconnected-(U1-SENSOR_VP-Pad4)") (class "Default")
      (node (ref "U1") (pin "4") (pinfunction "SENSOR_VP_4") (pintype "unspecified+no_connect"))
    )
    (net (code "68") (name "unconnected-(U2-VREF-Pad5)") (class "Default")
      (node (ref "U2") (pin "5") (pinfunction "VREF_5") (pintype "unspecified+no_connect"))
    )
    (net (code "69") (name "unconnected-(U4-CTS-Pad18)") (class "Default")
      (node (ref "U4") (pin "18") (pinfunction "CTS_18") (pintype "unspecified+no_connect"))
    )
    (net (code "70") (name "unconnected-(U4-DCD-Pad24)") (class "Default")
      (node (ref "U4") (pin "24") (pinfunction "DCD_24") (pintype "unspecified+no_connect"))
    )
    (net (code "71") (name "unconnected-(U4-DSR-Pad22)") (class "Default")
      (node (ref "U4") (pin "22") (pinfunction "DSR_22") (pintype "unspecified+no_connect"))
    )
    (net (code "72") (name "unconnected-(U4-EPAD-Pad25)") (class "Default")
      (node (ref "U4") (pin "25") (pinfunction "EPAD_25") (pintype "unspecified+no_connect"))
    )
    (net (code "73") (name "unconnected-(U4-GPIO.0-Pad14)") (class "Default")
      (node (ref "U4") (pin "14") (pinfunction "GPIO.0_14") (pintype "unspecified+no_connect"))
    )
    (net (code "74") (name "unconnected-(U4-GPIO.1-Pad13)") (class "Default")
      (node (ref "U4") (pin "13") (pinfunction "GPIO.1_13") (pintype "unspecified+no_connect"))
    )
    (net (code "75") (name "unconnected-(U4-GPIO.2-Pad12)") (class "Default")
      (node (ref "U4") (pin "12") (pinfunction "GPIO.2_12") (pintype "unspecified+no_connect"))
    )
    (net (code "76") (name "unconnected-(U4-GPIO.3-Pad11)") (class "Default")
      (node (ref "U4") (pin "11") (pinfunction "GPIO.3_11") (pintype "unspecified+no_connect"))
    )
    (net (code "77") (name "unconnected-(U4-NC-Pad10)") (class "Default")
      (node (ref "U4") (pin "10") (pinfunction "NC_10") (pintype "unspecified+no_connect"))
    )
    (net (code "78") (name "unconnected-(U4-RI-Pad1)") (class "Default")
      (node (ref "U4") (pin "1") (pinfunction "RI_1") (pintype "unspecified+no_connect"))
    )
    (net (code "79") (name "unconnected-(U4-SUSPEND#-Pad15)") (class "Default")
      (node (ref "U4") (pin "15") (pinfunction "SUSPEND#_15") (pintype "unspecified+no_connect"))
    )
    (net (code "80") (name "unconnected-(U4-SUSPEND-Pad17)") (class "Default")
      (node (ref "U4") (pin "17") (pinfunction "SUSPEND_17") (pintype "unspecified+no_connect"))
    )
    (net (code "81") (name "unconnected-(U4-VPP-Pad16)") (class "Default")
      (node (ref "U4") (pin "16") (pinfunction "VPP_16") (pintype "unspecified+no_connect"))
    )
    (net (code "82") (name "unconnected-(U7-INH-Pad8)") (class "Default")
      (node (ref "U7") (pin "8") (pinfunction "INH_8") (pintype "unspecified+no_connect"))
    )
    (net (code "83") (name "unconnected-(USB-C-SBU1-PadA8)") (class "Default")
      (node (ref "USB-C") (pin "A8") (pinfunction "SBU1_A8") (pintype "unspecified+no_connect"))
    )
    (net (code "84") (name "unconnected-(USB-C-SBU2-PadB8)") (class "Default")
      (node (ref "USB-C") (pin "B8") (pinfunction "SBU2_B8") (pintype "unspecified+no_connect"))
    )
  )
)
